# STM32F413Nucleo_NT35510__SCH.net
KiCad netlist of a schematic drawn in Altium Designer
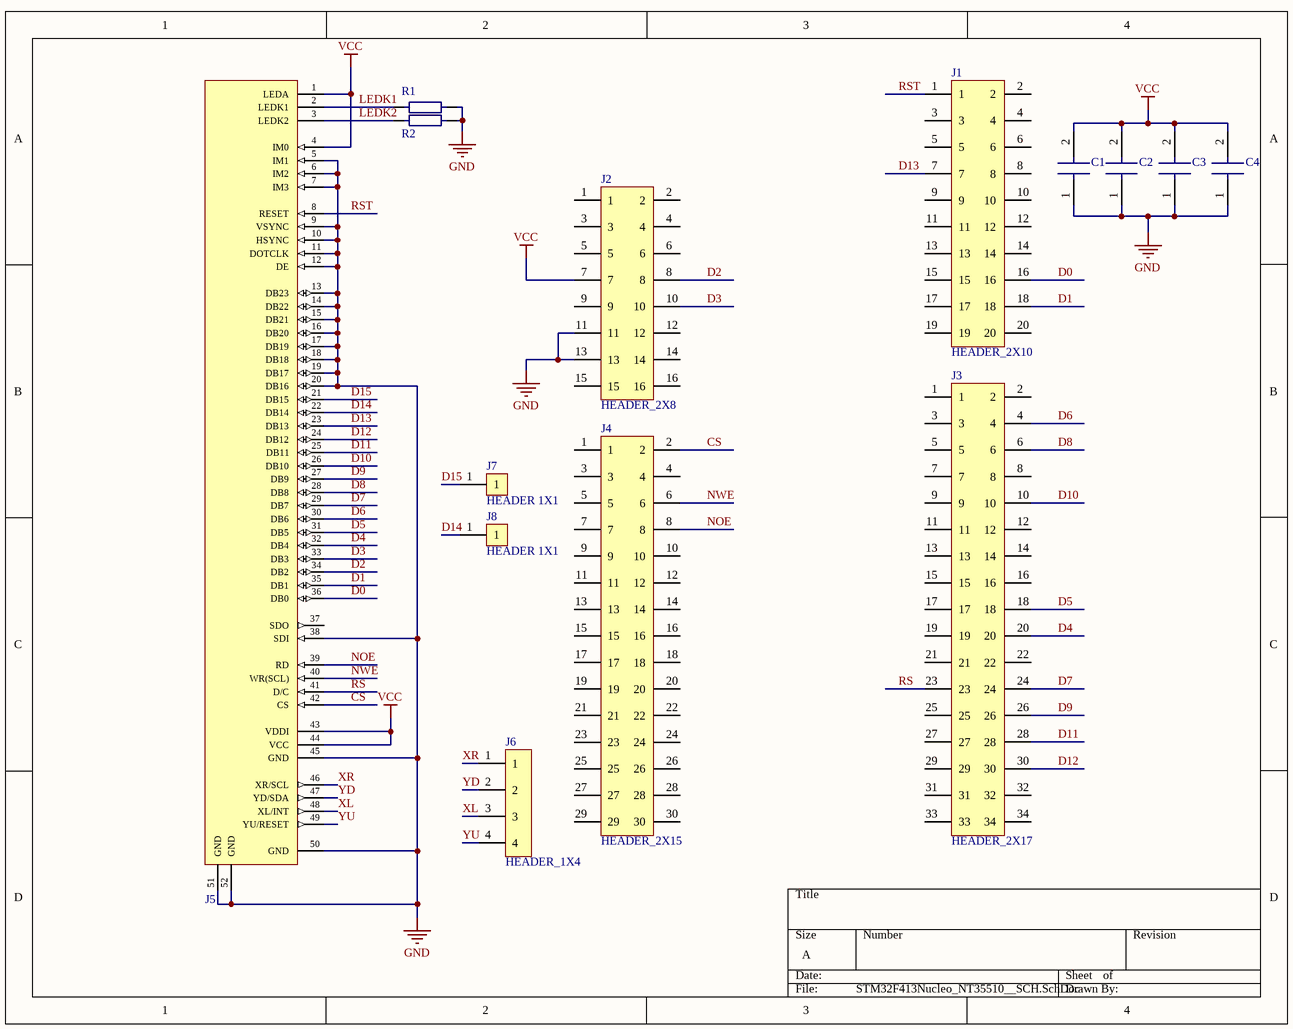
[diagram p0: STM32F413Nucleo_NT35510__SCH.SchDoc]

(export (version "E")
  (design (tool "Eeschema 10.0.6"))
  (components
    (comp (ref "C1")
      (value "Capacitor 0.1uf")
      (footprint "Capacitor 0805")
      (libsource (lib "STM32F413Nucleo_NT35510__SCHlib") (part "Capacitor 0.1uf"))
    )
    (comp (ref "C2")
      (value "Capacitor 10u")
      (footprint "Capacitor 0805")
      (libsource (lib "STM32F413Nucleo_NT35510__SCHlib") (part "Capacitor 10u"))
    )
    (comp (ref "C3")
      (value "Capacitor 10u")
      (footprint "Capacitor 0805")
      (libsource (lib "STM32F413Nucleo_NT35510__SCHlib") (part "Capacitor 10u"))
    )
    (comp (ref "C4")
      (value "Capacitor 0.1uf")
      (footprint "Capacitor 0805")
      (libsource (lib "STM32F413Nucleo_NT35510__SCHlib") (part "Capacitor 0.1uf"))
    )
    (comp (ref "J1")
      (value "HEADER_2X10")
      (footprint "HEADER_2X10")
      (description "Header, Dual row, 10-Pin")
      (libsource (lib "STM32F413Nucleo_NT35510__SCHlib") (part "HEADER_2X10"))
    )
    (comp (ref "J2")
      (value "HEADER_2X8")
      (footprint "HEADER_2x8")
      (description "Header, Dual row, 8-Pin")
      (libsource (lib "STM32F413Nucleo_NT35510__SCHlib") (part "HEADER_2X8"))
    )
    (comp (ref "J3")
      (value "HEADER_2X17")
      (footprint "HEADER_2X17")
      (description "Header, Dual row, 17-Pin")
      (libsource (lib "STM32F413Nucleo_NT35510__SCHlib") (part "HEADER_2X17"))
    )
    (comp (ref "J4")
      (value "HEADER_2X15")
      (footprint "HEADER_2x15")
      (description "Header, Dual row, 15-Pin")
      (libsource (lib "STM32F413Nucleo_NT35510__SCHlib") (part "HEADER_2X15"))
    )
    (comp (ref "J5")
      (value "NT35510_Controller")
      (footprint "ER-CON50HT-1")
      (description "NT35510 LCD Controller")
      (libsource (lib "STM32F413Nucleo_NT35510__SCHlib") (part "NT35510_Controller"))
    )
    (comp (ref "J6")
      (value "HEADER_1X4")
      (footprint "HEADER_1x4")
      (description "Header, Single row, 4-Pin")
      (libsource (lib "STM32F413Nucleo_NT35510__SCHlib") (part "HEADER_1X4"))
    )
    (comp (ref "J7")
      (value "HEADER 1X1")
      (footprint "HEADER_1X1")
      (description "Header, Single row, 1-Pin")
      (libsource (lib "STM32F413Nucleo_NT35510__SCHlib") (part "HEADER 1X1"))
    )
    (comp (ref "J8")
      (value "HEADER 1X1")
      (footprint "HEADER_1X1")
      (description "Header, Single row, 1-Pin")
      (libsource (lib "STM32F413Nucleo_NT35510__SCHlib") (part "HEADER 1X1"))
    )
    (comp (ref "R1")
      (value "Resistor 680R")
      (footprint "RES_0805(2012)")
      (description "Resistor")
      (libsource (lib "STM32F413Nucleo_NT35510__SCHlib") (part "Resistor 680R"))
    )
    (comp (ref "R2")
      (value "Resistor 680R")
      (footprint "RES_0805(2012)")
      (description "Resistor")
      (libsource (lib "STM32F413Nucleo_NT35510__SCHlib") (part "Resistor 680R"))
    )
  )
  (nets
    (net (code "1") (name "/CS") (class "Default")
      (node (ref "J4") (pin "2") (pinfunction "2_2") (pintype "passive"))
      (node (ref "J5") (pin "42") (pinfunction "CS_42") (pintype "input"))
    )
    (net (code "2") (name "/D0") (class "Default")
      (node (ref "J1") (pin "16") (pinfunction "16_16") (pintype "passive"))
      (node (ref "J5") (pin "36") (pinfunction "DB0_36") (pintype "bidirectional"))
    )
    (net (code "3") (name "/D1") (class "Default")
      (node (ref "J1") (pin "18") (pinfunction "18_18") (pintype "passive"))
      (node (ref "J5") (pin "35") (pinfunction "DB1_35") (pintype "bidirectional"))
    )
    (net (code "4") (name "/D2") (class "Default")
      (node (ref "J2") (pin "8") (pinfunction "8_8") (pintype "passive"))
      (node (ref "J5") (pin "34") (pinfunction "DB2_34") (pintype "bidirectional"))
    )
    (net (code "5") (name "/D3") (class "Default")
      (node (ref "J2") (pin "10") (pinfunction "10_10") (pintype "passive"))
      (node (ref "J5") (pin "33") (pinfunction "DB3_33") (pintype "bidirectional"))
    )
    (net (code "6") (name "/D4") (class "Default")
      (node (ref "J3") (pin "20") (pinfunction "20_20") (pintype "passive"))
      (node (ref "J5") (pin "32") (pinfunction "DB4_32") (pintype "bidirectional"))
    )
    (net (code "7") (name "/D5") (class "Default")
      (node (ref "J3") (pin "18") (pinfunction "18_18") (pintype "passive"))
      (node (ref "J5") (pin "31") (pinfunction "DB5_31") (pintype "bidirectional"))
    )
    (net (code "8") (name "/D6") (class "Default")
      (node (ref "J3") (pin "4") (pinfunction "4_4") (pintype "passive"))
      (node (ref "J5") (pin "30") (pinfunction "DB6_30") (pintype "bidirectional"))
    )
    (net (code "9") (name "/D7") (class "Default")
      (node (ref "J3") (pin "24") (pinfunction "24_24") (pintype "passive"))
      (node (ref "J5") (pin "29") (pinfunction "DB7_29") (pintype "bidirectional"))
    )
    (net (code "10") (name "/D8") (class "Default")
      (node (ref "J3") (pin "6") (pinfunction "6_6") (pintype "passive"))
      (node (ref "J5") (pin "28") (pinfunction "DB8_28") (pintype "bidirectional"))
    )
    (net (code "11") (name "/D9") (class "Default")
      (node (ref "J3") (pin "26") (pinfunction "26_26") (pintype "passive"))
      (node (ref "J5") (pin "27") (pinfunction "DB9_27") (pintype "bidirectional"))
    )
    (net (code "12") (name "/D10") (class "Default")
      (node (ref "J3") (pin "10") (pinfunction "10_10") (pintype "passive"))
      (node (ref "J5") (pin "26") (pinfunction "DB10_26") (pintype "bidirectional"))
    )
    (net (code "13") (name "/D11") (class "Default")
      (node (ref "J3") (pin "28") (pinfunction "28_28") (pintype "passive"))
      (node (ref "J5") (pin "25") (pinfunction "DB11_25") (pintype "bidirectional"))
    )
    (net (code "14") (name "/D12") (class "Default")
      (node (ref "J3") (pin "30") (pinfunction "30_30") (pintype "passive"))
      (node (ref "J5") (pin "24") (pinfunction "DB12_24") (pintype "bidirectional"))
    )
    (net (code "15") (name "/D13") (class "Default")
      (node (ref "J1") (pin "7") (pinfunction "7_7") (pintype "passive"))
      (node (ref "J5") (pin "23") (pinfunction "DB13_23") (pintype "bidirectional"))
    )
    (net (code "16") (name "/D14") (class "Default")
      (node (ref "J5") (pin "22") (pinfunction "DB14_22") (pintype "bidirectional"))
      (node (ref "J8") (pin "1") (pinfunction "1_1") (pintype "passive"))
    )
    (net (code "17") (name "/D15") (class "Default")
      (node (ref "J5") (pin "21") (pinfunction "DB15_21") (pintype "bidirectional"))
      (node (ref "J7") (pin "1") (pinfunction "1_1") (pintype "passive"))
    )
    (net (code "18") (name "/LEDK1") (class "Default")
      (node (ref "J5") (pin "2") (pinfunction "LEDK1_2") (pintype "power_in"))
      (node (ref "R1") (pin "1") (pinfunction "1_1") (pintype "passive"))
    )
    (net (code "19") (name "/LEDK2") (class "Default")
      (node (ref "J5") (pin "3") (pinfunction "LEDK2_3") (pintype "power_in"))
      (node (ref "R2") (pin "1") (pinfunction "1_1") (pintype "passive"))
    )
    (net (code "20") (name "/NOE") (class "Default")
      (node (ref "J4") (pin "8") (pinfunction "8_8") (pintype "passive"))
      (node (ref "J5") (pin "39") (pinfunction "RD_39") (pintype "input"))
    )
    (net (code "21") (name "/NWE") (class "Default")
      (node (ref "J4") (pin "6") (pinfunction "6_6") (pintype "passive"))
      (node (ref "J5") (pin "40") (pinfunction "WR(SCL)_40") (pintype "input"))
    )
    (net (code "22") (name "/RS") (class "Default")
      (node (ref "J3") (pin "23") (pinfunction "23_23") (pintype "passive"))
      (node (ref "J5") (pin "41") (pinfunction "D/C_41") (pintype "input"))
    )
    (net (code "23") (name "/RST") (class "Default")
      (node (ref "J1") (pin "1") (pinfunction "1_1") (pintype "passive"))
      (node (ref "J5") (pin "8") (pinfunction "RESET_8") (pintype "input"))
    )
    (net (code "24") (name "/XL") (class "Default")
      (node (ref "J5") (pin "48") (pinfunction "XL/INT_48") (pintype "output"))
      (node (ref "J6") (pin "3") (pinfunction "3_3") (pintype "passive"))
    )
    (net (code "25") (name "/XR") (class "Default")
      (node (ref "J5") (pin "46") (pinfunction "XR/SCL_46") (pintype "output"))
      (node (ref "J6") (pin "1") (pinfunction "1_1") (pintype "passive"))
    )
    (net (code "26") (name "/YD") (class "Default")
      (node (ref "J5") (pin "47") (pinfunction "YD/SDA_47") (pintype "output"))
      (node (ref "J6") (pin "2") (pinfunction "2_2") (pintype "passive"))
    )
    (net (code "27") (name "/YU") (class "Default")
      (node (ref "J5") (pin "49") (pinfunction "YU/RESET_49") (pintype "output"))
      (node (ref "J6") (pin "4") (pinfunction "4_4") (pintype "passive"))
    )
    (net (code "28") (name "GND") (class "Default")
      (node (ref "C1") (pin "1") (pinfunction "1_1") (pintype "passive"))
      (node (ref "C2") (pin "1") (pinfunction "1_1") (pintype "passive"))
      (node (ref "C3") (pin "1") (pinfunction "1_1") (pintype "passive"))
      (node (ref "C4") (pin "1") (pinfunction "1_1") (pintype "passive"))
      (node (ref "J2") (pin "11") (pinfunction "11_11") (pintype "passive"))
      (node (ref "J2") (pin "13") (pinfunction "13_13") (pintype "passive"))
      (node (ref "J5") (pin "10") (pinfunction "HSYNC_10") (pintype "input"))
      (node (ref "J5") (pin "11") (pinfunction "DOTCLK_11") (pintype "input"))
      (node (ref "J5") (pin "12") (pinfunction "DE_12") (pintype "input"))
      (node (ref "J5") (pin "13") (pinfunction "DB23_13") (pintype "bidirectional"))
      (node (ref "J5") (pin "14") (pinfunction "DB22_14") (pintype "bidirectional"))
      (node (ref "J5") (pin "15") (pinfunction "DB21_15") (pintype "bidirectional"))
      (node (ref "J5") (pin "16") (pinfunction "DB20_16") (pintype "bidirectional"))
      (node (ref "J5") (pin "17") (pinfunction "DB19_17") (pintype "bidirectional"))
      (node (ref "J5") (pin "18") (pinfunction "DB18_18") (pintype "bidirectional"))
      (node (ref "J5") (pin "19") (pinfunction "DB17_19") (pintype "bidirectional"))
      (node (ref "J5") (pin "20") (pinfunction "DB16_20") (pintype "bidirectional"))
      (node (ref "J5") (pin "38") (pinfunction "SDI_38") (pintype "input"))
      (node (ref "J5") (pin "45") (pinfunction "GND_45") (pintype "power_in"))
      (node (ref "J5") (pin "5") (pinfunction "IM1_5") (pintype "input"))
      (node (ref "J5") (pin "50") (pinfunction "GND_50") (pintype "power_in"))
      (node (ref "J5") (pin "51") (pinfunction "GND_51") (pintype "power_in"))
      (node (ref "J5") (pin "52") (pinfunction "GND_52") (pintype "power_in"))
      (node (ref "J5") (pin "6") (pinfunction "IM2_6") (pintype "input"))
      (node (ref "J5") (pin "7") (pinfunction "IM3_7") (pintype "input"))
      (node (ref "J5") (pin "9") (pinfunction "VSYNC_9") (pintype "input"))
      (node (ref "R1") (pin "2") (pinfunction "2_2") (pintype "passive"))
      (node (ref "R2") (pin "2") (pinfunction "2_2") (pintype "passive"))
    )
    (net (code "29") (name "VCC") (class "Default")
      (node (ref "C1") (pin "2") (pinfunction "2_2") (pintype "passive"))
      (node (ref "C2") (pin "2") (pinfunction "2_2") (pintype "passive"))
      (node (ref "C3") (pin "2") (pinfunction "2_2") (pintype "passive"))
      (node (ref "C4") (pin "2") (pinfunction "2_2") (pintype "passive"))
      (node (ref "J2") (pin "7") (pinfunction "7_7") (pintype "passive"))
      (node (ref "J5") (pin "1") (pinfunction "LEDA_1") (pintype "power_in"))
      (node (ref "J5") (pin "4") (pinfunction "IM0_4") (pintype "input"))
      (node (ref "J5") (pin "43") (pinfunction "VDDI_43") (pintype "power_in"))
      (node (ref "J5") (pin "44") (pinfunction "VCC_44") (pintype "power_in"))
    )
    (net (code "30") (name "unconnected-(J1-Pad2)") (class "Default")
      (node (ref "J1") (pin "2") (pinfunction "2_2") (pintype "passive"))
    )
    (net (code "31") (name "unconnected-(J1-Pad3)") (class "Default")
      (node (ref "J1") (pin "3") (pinfunction "3_3") (pintype "passive"))
    )
    (net (code "32") (name "unconnected-(J1-Pad4)") (class "Default")
      (node (ref "J1") (pin "4") (pinfunction "4_4") (pintype "passive"))
    )
    (net (code "33") (name "unconnected-(J1-Pad5)") (class "Default")
      (node (ref "J1") (pin "5") (pinfunction "5_5") (pintype "passive"))
    )
    (net (code "34") (name "unconnected-(J1-Pad6)") (class "Default")
      (node (ref "J1") (pin "6") (pinfunction "6_6") (pintype "passive"))
    )
    (net (code "35") (name "unconnected-(J1-Pad8)") (class "Default")
      (node (ref "J1") (pin "8") (pinfunction "8_8") (pintype "passive"))
    )
    (net (code "36") (name "unconnected-(J1-Pad9)") (class "Default")
      (node (ref "J1") (pin "9") (pinfunction "9_9") (pintype "passive"))
    )
    (net (code "37") (name "unconnected-(J1-Pad10)") (class "Default")
      (node (ref "J1") (pin "10") (pinfunction "10_10") (pintype "passive"))
    )
    (net (code "38") (name "unconnected-(J1-Pad11)") (class "Default")
      (node (ref "J1") (pin "11") (pinfunction "11_11") (pintype "passive"))
    )
    (net (code "39") (name "unconnected-(J1-Pad12)") (class "Default")
      (node (ref "J1") (pin "12") (pinfunction "12_12") (pintype "passive"))
    )
    (net (code "40") (name "unconnected-(J1-Pad13)") (class "Default")
      (node (ref "J1") (pin "13") (pinfunction "13_13") (pintype "passive"))
    )
    (net (code "41") (name "unconnected-(J1-Pad14)") (class "Default")
      (node (ref "J1") (pin "14") (pinfunction "14_14") (pintype "passive"))
    )
    (net (code "42") (name "unconnected-(J1-Pad15)") (class "Default")
      (node (ref "J1") (pin "15") (pinfunction "15_15") (pintype "passive"))
    )
    (net (code "43") (name "unconnected-(J1-Pad17)") (class "Default")
      (node (ref "J1") (pin "17") (pinfunction "17_17") (pintype "passive"))
    )
    (net (code "44") (name "unconnected-(J1-Pad19)") (class "Default")
      (node (ref "J1") (pin "19") (pinfunction "19_19") (pintype "passive"))
    )
    (net (code "45") (name "unconnected-(J1-Pad20)") (class "Default")
      (node (ref "J1") (pin "20") (pinfunction "20_20") (pintype "passive"))
    )
    (net (code "46") (name "unconnected-(J2-Pad1)") (class "Default")
      (node (ref "J2") (pin "1") (pinfunction "1_1") (pintype "passive"))
    )
    (net (code "47") (name "unconnected-(J2-Pad2)") (class "Default")
      (node (ref "J2") (pin "2") (pinfunction "2_2") (pintype "passive"))
    )
    (net (code "48") (name "unconnected-(J2-Pad3)") (class "Default")
      (node (ref "J2") (pin "3") (pinfunction "3_3") (pintype "passive"))
    )
    (net (code "49") (name "unconnected-(J2-Pad4)") (class "Default")
      (node (ref "J2") (pin "4") (pinfunction "4_4") (pintype "passive"))
    )
    (net (code "50") (name "unconnected-(J2-Pad5)") (class "Default")
      (node (ref "J2") (pin "5") (pinfunction "5_5") (pintype "passive"))
    )
    (net (code "51") (name "unconnected-(J2-Pad6)") (class "Default")
      (node (ref "J2") (pin "6") (pinfunction "6_6") (pintype "passive"))
    )
    (net (code "52") (name "unconnected-(J2-Pad9)") (class "Default")
      (node (ref "J2") (pin "9") (pinfunction "9_9") (pintype "passive"))
    )
    (net (code "53") (name "unconnected-(J2-Pad12)") (class "Default")
      (node (ref "J2") (pin "12") (pinfunction "12_12") (pintype "passive"))
    )
    (net (code "54") (name "unconnected-(J2-Pad14)") (class "Default")
      (node (ref "J2") (pin "14") (pinfunction "14_14") (pintype "passive"))
    )
    (net (code "55") (name "unconnected-(J2-Pad15)") (class "Default")
      (node (ref "J2") (pin "15") (pinfunction "15_15") (pintype "passive"))
    )
    (net (code "56") (name "unconnected-(J2-Pad16)") (class "Default")
      (node (ref "J2") (pin "16") (pinfunction "16_16") (pintype "passive"))
    )
    (net (code "57") (name "unconnected-(J3-Pad1)") (class "Default")
      (node (ref "J3") (pin "1") (pinfunction "1_1") (pintype "passive"))
    )
    (net (code "58") (name "unconnected-(J3-Pad2)") (class "Default")
      (node (ref "J3") (pin "2") (pinfunction "2_2") (pintype "passive"))
    )
    (net (code "59") (name "unconnected-(J3-Pad3)") (class "Default")
      (node (ref "J3") (pin "3") (pinfunction "3_3") (pintype "passive"))
    )
    (net (code "60") (name "unconnected-(J3-Pad5)") (class "Default")
      (node (ref "J3") (pin "5") (pinfunction "5_5") (pintype "passive"))
    )
    (net (code "61") (name "unconnected-(J3-Pad7)") (class "Default")
      (node (ref "J3") (pin "7") (pinfunction "7_7") (pintype "passive"))
    )
    (net (code "62") (name "unconnected-(J3-Pad8)") (class "Default")
      (node (ref "J3") (pin "8") (pinfunction "8_8") (pintype "passive"))
    )
    (net (code "63") (name "unconnected-(J3-Pad9)") (class "Default")
      (node (ref "J3") (pin "9") (pinfunction "9_9") (pintype "passive"))
    )
    (net (code "64") (name "unconnected-(J3-Pad11)") (class "Default")
      (node (ref "J3") (pin "11") (pinfunction "11_11") (pintype "passive"))
    )
    (net (code "65") (name "unconnected-(J3-Pad12)") (class "Default")
      (node (ref "J3") (pin "12") (pinfunction "12_12") (pintype "passive"))
    )
    (net (code "66") (name "unconnected-(J3-Pad13)") (class "Default")
      (node (ref "J3") (pin "13") (pinfunction "13_13") (pintype "passive"))
    )
    (net (code "67") (name "unconnected-(J3-Pad14)") (class "Default")
      (node (ref "J3") (pin "14") (pinfunction "14_14") (pintype "passive"))
    )
    (net (code "68") (name "unconnected-(J3-Pad15)") (class "Default")
      (node (ref "J3") (pin "15") (pinfunction "15_15") (pintype "passive"))
    )
    (net (code "69") (name "unconnected-(J3-Pad16)") (class "Default")
      (node (ref "J3") (pin "16") (pinfunction "16_16") (pintype "passive"))
    )
    (net (code "70") (name "unconnected-(J3-Pad17)") (class "Default")
      (node (ref "J3") (pin "17") (pinfunction "17_17") (pintype "passive"))
    )
    (net (code "71") (name "unconnected-(J3-Pad19)") (class "Default")
      (node (ref "J3") (pin "19") (pinfunction "19_19") (pintype "passive"))
    )
    (net (code "72") (name "unconnected-(J3-Pad21)") (class "Default")
      (node (ref "J3") (pin "21") (pinfunction "21_21") (pintype "passive"))
    )
    (net (code "73") (name "unconnected-(J3-Pad22)") (class "Default")
      (node (ref "J3") (pin "22") (pinfunction "22_22") (pintype "passive"))
    )
    (net (code "74") (name "unconnected-(J3-Pad25)") (class "Default")
      (node (ref "J3") (pin "25") (pinfunction "25_25") (pintype "passive"))
    )
    (net (code "75") (name "unconnected-(J3-Pad27)") (class "Default")
      (node (ref "J3") (pin "27") (pinfunction "27_27") (pintype "passive"))
    )
    (net (code "76") (name "unconnected-(J3-Pad29)") (class "Default")
      (node (ref "J3") (pin "29") (pinfunction "29_29") (pintype "passive"))
    )
    (net (code "77") (name "unconnected-(J3-Pad31)") (class "Default")
      (node (ref "J3") (pin "31") (pinfunction "31_31") (pintype "passive"))
    )
    (net (code "78") (name "unconnected-(J3-Pad32)") (class "Default")
      (node (ref "J3") (pin "32") (pinfunction "32_32") (pintype "passive"))
    )
    (net (code "79") (name "unconnected-(J3-Pad33)") (class "Default")
      (node (ref "J3") (pin "33") (pinfunction "33_33") (pintype "passive"))
    )
    (net (code "80") (name "unconnected-(J3-Pad34)") (class "Default")
      (node (ref "J3") (pin "34") (pinfunction "34_34") (pintype "passive"))
    )
    (net (code "81") (name "unconnected-(J4-Pad1)") (class "Default")
      (node (ref "J4") (pin "1") (pinfunction "1_1") (pintype "passive"))
    )
    (net (code "82") (name "unconnected-(J4-Pad3)") (class "Default")
      (node (ref "J4") (pin "3") (pinfunction "3_3") (pintype "passive"))
    )
    (net (code "83") (name "unconnected-(J4-Pad4)") (class "Default")
      (node (ref "J4") (pin "4") (pinfunction "4_4") (pintype "passive"))
    )
    (net (code "84") (name "unconnected-(J4-Pad5)") (class "Default")
      (node (ref "J4") (pin "5") (pinfunction "5_5") (pintype "passive"))
    )
    (net (code "85") (name "unconnected-(J4-Pad7)") (class "Default")
      (node (ref "J4") (pin "7") (pinfunction "7_7") (pintype "passive"))
    )
    (net (code "86") (name "unconnected-(J4-Pad9)") (class "Default")
      (node (ref "J4") (pin "9") (pinfunction "9_9") (pintype "passive"))
    )
    (net (code "87") (name "unconnected-(J4-Pad10)") (class "Default")
      (node (ref "J4") (pin "10") (pinfunction "10_10") (pintype "passive"))
    )
    (net (code "88") (name "unconnected-(J4-Pad11)") (class "Default")
      (node (ref "J4") (pin "11") (pinfunction "11_11") (pintype "passive"))
    )
    (net (code "89") (name "unconnected-(J4-Pad12)") (class "Default")
      (node (ref "J4") (pin "12") (pinfunction "12_12") (pintype "passive"))
    )
    (net (code "90") (name "unconnected-(J4-Pad13)") (class "Default")
      (node (ref "J4") (pin "13") (pinfunction "13_13") (pintype "passive"))
    )
    (net (code "91") (name "unconnected-(J4-Pad14)") (class "Default")
      (node (ref "J4") (pin "14") (pinfunction "14_14") (pintype "passive"))
    )
    (net (code "92") (name "unconnected-(J4-Pad15)") (class "Default")
      (node (ref "J4") (pin "15") (pinfunction "15_15") (pintype "passive"))
    )
    (net (code "93") (name "unconnected-(J4-Pad16)") (class "Default")
      (node (ref "J4") (pin "16") (pinfunction "16_16") (pintype "passive"))
    )
    (net (code "94") (name "unconnected-(J4-Pad17)") (class "Default")
      (node (ref "J4") (pin "17") (pinfunction "17_17") (pintype "passive"))
    )
    (net (code "95") (name "unconnected-(J4-Pad18)") (class "Default")
      (node (ref "J4") (pin "18") (pinfunction "18_18") (pintype "passive"))
    )
    (net (code "96") (name "unconnected-(J4-Pad19)") (class "Default")
      (node (ref "J4") (pin "19") (pinfunction "19_19") (pintype "passive"))
    )
    (net (code "97") (name "unconnected-(J4-Pad20)") (class "Default")
      (node (ref "J4") (pin "20") (pinfunction "20_20") (pintype "passive"))
    )
    (net (code "98") (name "unconnected-(J4-Pad21)") (class "Default")
      (node (ref "J4") (pin "21") (pinfunction "21_21") (pintype "passive"))
    )
    (net (code "99") (name "unconnected-(J4-Pad22)") (class "Default")
      (node (ref "J4") (pin "22") (pinfunction "22_22") (pintype "passive"))
    )
    (net (code "100") (name "unconnected-(J4-Pad23)") (class "Default")
      (node (ref "J4") (pin "23") (pinfunction "23_23") (pintype "passive"))
    )
    (net (code "101") (name "unconnected-(J4-Pad24)") (class "Default")
      (node (ref "J4") (pin "24") (pinfunction "24_24") (pintype "passive"))
    )
    (net (code "102") (name "unconnected-(J4-Pad25)") (class "Default")
      (node (ref "J4") (pin "25") (pinfunction "25_25") (pintype "passive"))
    )
    (net (code "103") (name "unconnected-(J4-Pad26)") (class "Default")
      (node (ref "J4") (pin "26") (pinfunction "26_26") (pintype "passive"))
    )
    (net (code "104") (name "unconnected-(J4-Pad27)") (class "Default")
      (node (ref "J4") (pin "27") (pinfunction "27_27") (pintype "passive"))
    )
    (net (code "105") (name "unconnected-(J4-Pad28)") (class "Default")
      (node (ref "J4") (pin "28") (pinfunction "28_28") (pintype "passive"))
    )
    (net (code "106") (name "unconnected-(J4-Pad29)") (class "Default")
      (node (ref "J4") (pin "29") (pinfunction "29_29") (pintype "passive"))
    )
    (net (code "107") (name "unconnected-(J4-Pad30)") (class "Default")
      (node (ref "J4") (pin "30") (pinfunction "30_30") (pintype "passive"))
    )
    (net (code "108") (name "unconnected-(J5-SDO-Pad37)") (class "Default")
      (node (ref "J5") (pin "37") (pinfunction "SDO_37") (pintype "output"))
    )
  )
)
